# Kuga2.net
KiCad netlist of a schematic drawn in EAGLE
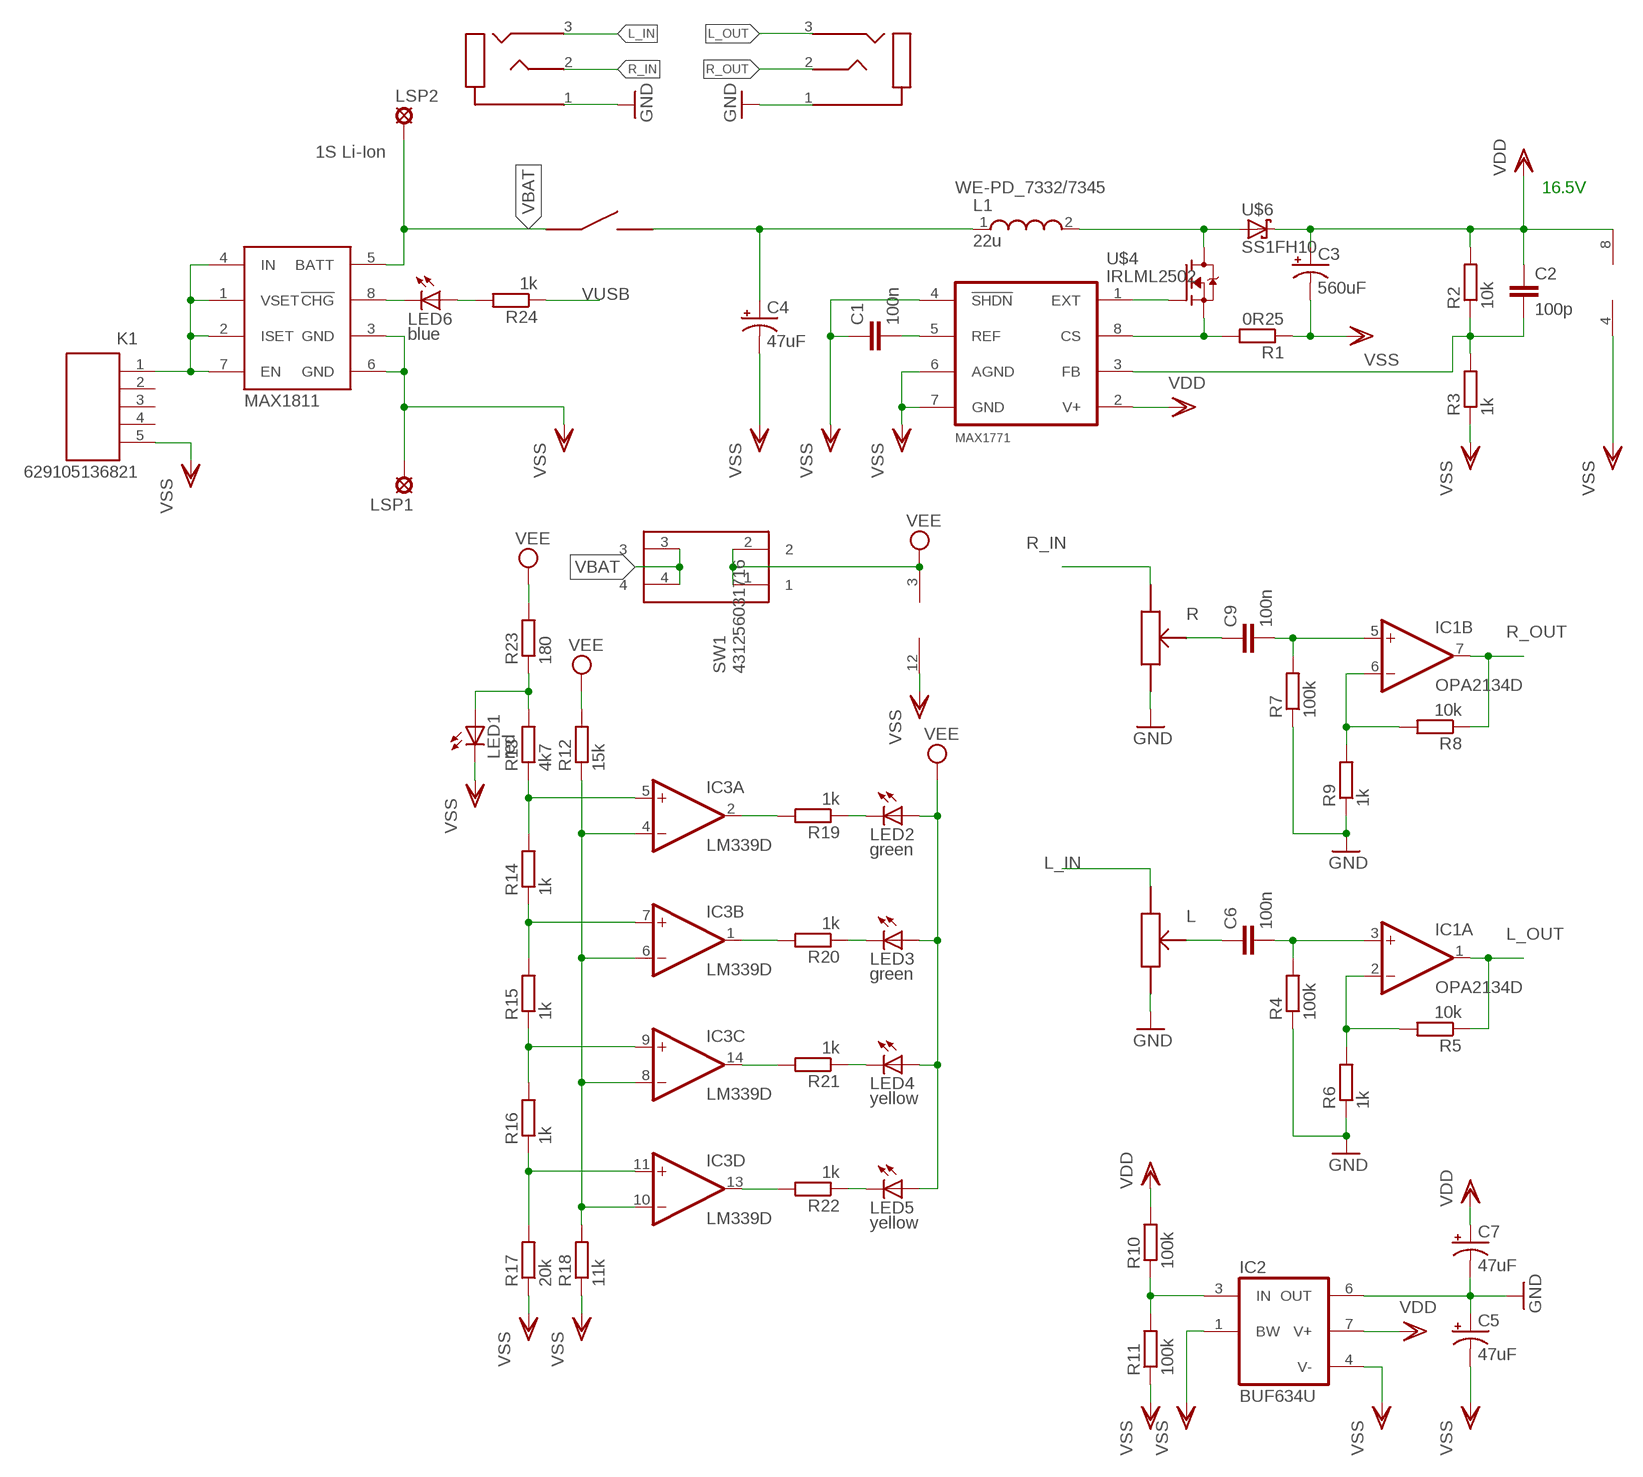
[diagram p0: schematic, sheet 1]

(export (version "E")
  (design (tool "Eeschema 10.0.6"))
  (components
    (comp (ref "C1")
      (value "100n")
      (footprint "eagle-import:C0603K")
      (libsource (lib "eagle-import") (part "C-EUC0603K"))
    )
    (comp (ref "C2")
      (value "100p")
      (footprint "eagle-import:C0603")
      (libsource (lib "eagle-import") (part "C-EUC0603"))
    )
    (comp (ref "C3")
      (value "560uF")
      (footprint "eagle-import:PANASONIC_G")
      (libsource (lib "eagle-import") (part "560UF-PANASONIC_G-25V-20%"))
    )
    (comp (ref "C4")
      (value "47uF")
      (footprint "eagle-import:PANASONIC_D")
      (libsource (lib "eagle-import") (part "47UF-POLAR-PANASONIC_D-35V-20%"))
    )
    (comp (ref "C5")
      (value "47uF")
      (footprint "eagle-import:PANASONIC_D")
      (libsource (lib "eagle-import") (part "47UF-POLAR-PANASONIC_D-35V-20%"))
    )
    (comp (ref "C6")
      (value "100n")
      (footprint "eagle-import:C1206")
      (libsource (lib "eagle-import") (part "C-EUC1206"))
    )
    (comp (ref "C7")
      (value "47uF")
      (footprint "eagle-import:PANASONIC_D")
      (libsource (lib "eagle-import") (part "47UF-POLAR-PANASONIC_D-35V-20%"))
    )
    (comp (ref "C9")
      (value "100n")
      (footprint "eagle-import:C1206")
      (libsource (lib "eagle-import") (part "C-EUC1206"))
    )
    (comp (ref "IC1")
      (value "OPA2134D")
      (footprint "eagle-import:SOIC8")
      (libsource (lib "eagle-import") (part "OPA2134D"))
    )
    (comp (ref "IC2")
      (value "BUF634U")
      (footprint "eagle-import:SO08")
      (fields (field (name "MF") "TEXAS INSTRUMENTS"))
      (libsource (lib "eagle-import") (part "BUF634U"))
    )
    (comp (ref "IC3")
      (value "LM339D")
      (footprint "eagle-import:SO14")
      (libsource (lib "eagle-import") (part "LM339D"))
    )
    (comp (ref "K1")
      (value "629105136821")
      (footprint "eagle-import:629105136821")
      (libsource (lib "eagle-import") (part "629105136821"))
    )
    (comp (ref "L1")
      (value "22u")
      (footprint "eagle-import:WE-PD_7332_7345")
      (libsource (lib "eagle-import") (part "WE-PD_7332/7345"))
    )
    (comp (ref "LED1")
      (value "red")
      (footprint "eagle-import:CHIP-LED0603")
      (libsource (lib "eagle-import") (part "LEDCHIP-LED0603"))
    )
    (comp (ref "LED2")
      (value "green")
      (footprint "eagle-import:CHIP-LED0603")
      (libsource (lib "eagle-import") (part "LEDCHIP-LED0603"))
    )
    (comp (ref "LED3")
      (value "green")
      (footprint "eagle-import:CHIP-LED0603")
      (libsource (lib "eagle-import") (part "LEDCHIP-LED0603"))
    )
    (comp (ref "LED4")
      (value "yellow")
      (footprint "eagle-import:CHIP-LED0603")
      (libsource (lib "eagle-import") (part "LEDCHIP-LED0603"))
    )
    (comp (ref "LED5")
      (value "yellow")
      (footprint "eagle-import:CHIP-LED0603")
      (libsource (lib "eagle-import") (part "LEDCHIP-LED0603"))
    )
    (comp (ref "LED6")
      (value "blue")
      (footprint "eagle-import:CHIP-LED0603")
      (libsource (lib "eagle-import") (part "LEDCHIP-LED0603"))
    )
    (comp (ref "LSP1")
      (value "LSP10")
      (footprint "eagle-import:LSP10")
      (libsource (lib "eagle-import") (part "LSP10"))
    )
    (comp (ref "LSP2")
      (value "LSP10")
      (footprint "eagle-import:LSP10")
      (libsource (lib "eagle-import") (part "LSP10"))
    )
    (comp (ref "MAX1771")
      (value "MAX1771")
      (footprint "eagle-import:SO-08")
      (libsource (lib "eagle-import") (part "MAX1771"))
    )
    (comp (ref "MAX1811")
      (value "MAX1811")
      (footprint "eagle-import:SO-08")
      (libsource (lib "eagle-import") (part "MAX1811"))
    )
    (comp (ref "R1")
      (value "0R25")
      (footprint "eagle-import:M3216")
      (libsource (lib "eagle-import") (part "R-EU_M3216"))
    )
    (comp (ref "R2")
      (value "10k")
      (footprint "eagle-import:R0603")
      (libsource (lib "eagle-import") (part "R-EU_R0603"))
    )
    (comp (ref "R3")
      (value "1k")
      (footprint "eagle-import:R0603")
      (libsource (lib "eagle-import") (part "R-EU_R0603"))
    )
    (comp (ref "R4")
      (value "100k")
      (footprint "eagle-import:R1206")
      (libsource (lib "eagle-import") (part "R-EU_R1206"))
    )
    (comp (ref "R5")
      (value "10k")
      (footprint "eagle-import:R1206")
      (libsource (lib "eagle-import") (part "R-EU_R1206"))
    )
    (comp (ref "R6")
      (value "1k")
      (footprint "eagle-import:R1206")
      (libsource (lib "eagle-import") (part "R-EU_R1206"))
    )
    (comp (ref "R7")
      (value "100k")
      (footprint "eagle-import:R1206")
      (libsource (lib "eagle-import") (part "R-EU_R1206"))
    )
    (comp (ref "R8")
      (value "10k")
      (footprint "eagle-import:R1206")
      (libsource (lib "eagle-import") (part "R-EU_R1206"))
    )
    (comp (ref "R9")
      (value "1k")
      (footprint "eagle-import:R1206")
      (libsource (lib "eagle-import") (part "R-EU_R1206"))
    )
    (comp (ref "R10")
      (value "100k")
      (footprint "eagle-import:R0603")
      (libsource (lib "eagle-import") (part "R-EU_R0603"))
    )
    (comp (ref "R11")
      (value "100k")
      (footprint "eagle-import:R0603")
      (libsource (lib "eagle-import") (part "R-EU_R0603"))
    )
    (comp (ref "R12")
      (value "15k")
      (footprint "eagle-import:R0603")
      (libsource (lib "eagle-import") (part "R-EU_R0603"))
    )
    (comp (ref "R13")
      (value "4k7")
      (footprint "eagle-import:R0603")
      (libsource (lib "eagle-import") (part "R-EU_R0603"))
    )
    (comp (ref "R14")
      (value "1k")
      (footprint "eagle-import:R0603")
      (libsource (lib "eagle-import") (part "R-EU_R0603"))
    )
    (comp (ref "R15")
      (value "1k")
      (footprint "eagle-import:R0603")
      (libsource (lib "eagle-import") (part "R-EU_R0603"))
    )
    (comp (ref "R16")
      (value "1k")
      (footprint "eagle-import:R0603")
      (libsource (lib "eagle-import") (part "R-EU_R0603"))
    )
    (comp (ref "R17")
      (value "20k")
      (footprint "eagle-import:R0603")
      (libsource (lib "eagle-import") (part "R-EU_R0603"))
    )
    (comp (ref "R18")
      (value "11k")
      (footprint "eagle-import:R0603")
      (libsource (lib "eagle-import") (part "R-EU_R0603"))
    )
    (comp (ref "R19")
      (value "1k")
      (footprint "eagle-import:R0603")
      (libsource (lib "eagle-import") (part "R-EU_R0603"))
    )
    (comp (ref "R20")
      (value "1k")
      (footprint "eagle-import:R0603")
      (libsource (lib "eagle-import") (part "R-EU_R0603"))
    )
    (comp (ref "R21")
      (value "1k")
      (footprint "eagle-import:R0603")
      (libsource (lib "eagle-import") (part "R-EU_R0603"))
    )
    (comp (ref "R22")
      (value "1k")
      (footprint "eagle-import:R0603")
      (libsource (lib "eagle-import") (part "R-EU_R0603"))
    )
    (comp (ref "R23")
      (value "180")
      (footprint "eagle-import:R0603")
      (libsource (lib "eagle-import") (part "R-EU_R0603"))
    )
    (comp (ref "R24")
      (value "1k")
      (footprint "eagle-import:R0603")
      (libsource (lib "eagle-import") (part "R-EU_R0603"))
    )
    (comp (ref "SW1")
      (value "431256031716")
      (footprint "eagle-import:431256031716")
      (libsource (lib "eagle-import") (part "431256031716"))
    )
    (comp (ref "U$1")
      (value "SJ1-3515-SMT-TR")
      (footprint "eagle-import:STX-35332-3N-TR")
      (libsource (lib "eagle-import") (part "SJ1-3515-SMT-TR"))
    )
    (comp (ref "U$2")
      (value "SJ1-3515-SMT-TR")
      (footprint "eagle-import:STX-35332-3N-TR")
      (libsource (lib "eagle-import") (part "SJ1-3515-SMT-TR"))
    )
    (comp (ref "U$4")
      (value "IRLML2502")
      (footprint "eagle-import:SOT23")
      (libsource (lib "eagle-import") (part "IRLML2502"))
    )
    (comp (ref "U$5")
      (value "PTR90")
      (footprint "eagle-import:PTR902")
      (libsource (lib "eagle-import") (part "PTR90"))
    )
    (comp (ref "U$6")
      (value "SS1FH10")
      (footprint "eagle-import:DO-219AB")
      (libsource (lib "eagle-import") (part "SS1FH10"))
    )
  )
  (nets
    (net (code "1") (name "/L") (class "Default")
      (node (ref "C6") (pin "1") (pinfunction "1_1") (pintype "passive"))
      (node (ref "U$5") (pin "R22") (pinfunction "12_R22") (pintype "bidirectional"))
    )
    (net (code "2") (name "/R") (class "Default")
      (node (ref "C9") (pin "1") (pinfunction "1_1") (pintype "passive"))
      (node (ref "U$5") (pin "R12") (pinfunction "12_R12") (pintype "bidirectional"))
    )
    (net (code "3") (name "/VUSB") (class "Default")
      (node (ref "K1") (pin "1") (pinfunction "1_1") (pintype "passive"))
      (node (ref "MAX1811") (pin "1") (pinfunction "VSET_1") (pintype "bidirectional"))
      (node (ref "MAX1811") (pin "2") (pinfunction "ISET_2") (pintype "bidirectional"))
      (node (ref "MAX1811") (pin "4") (pinfunction "IN_4") (pintype "bidirectional"))
      (node (ref "MAX1811") (pin "7") (pinfunction "EN_7") (pintype "bidirectional"))
      (node (ref "R24") (pin "1") (pinfunction "1_1") (pintype "passive"))
    )
    (net (code "4") (name "GND") (class "Default")
      (node (ref "C5") (pin "+") (pinfunction "+_+") (pintype "passive"))
      (node (ref "C7") (pin "-") (pinfunction "-_-") (pintype "passive"))
      (node (ref "IC2") (pin "6") (pinfunction "OUT_6") (pintype "output"))
      (node (ref "R4") (pin "1") (pinfunction "1_1") (pintype "passive"))
      (node (ref "R6") (pin "1") (pinfunction "1_1") (pintype "passive"))
      (node (ref "R7") (pin "1") (pinfunction "1_1") (pintype "passive"))
      (node (ref "R9") (pin "1") (pinfunction "1_1") (pintype "passive"))
      (node (ref "U$1") (pin "1") (pinfunction "SLEEVE_1") (pintype "bidirectional"))
      (node (ref "U$2") (pin "1") (pinfunction "SLEEVE_1") (pintype "bidirectional"))
      (node (ref "U$5") (pin "R13") (pinfunction "13_R13") (pintype "bidirectional"))
      (node (ref "U$5") (pin "R23") (pinfunction "13_R23") (pintype "bidirectional"))
    )
    (net (code "5") (name "L_IN") (class "Default")
      (node (ref "U$2") (pin "3") (pinfunction "RING_3") (pintype "bidirectional"))
      (node (ref "U$5") (pin "R21") (pinfunction "11_R21") (pintype "bidirectional"))
    )
    (net (code "6") (name "L_OUT") (class "Default")
      (node (ref "IC1") (pin "1") (pinfunction "OUT_1") (pintype "output"))
      (node (ref "R5") (pin "1") (pinfunction "1_1") (pintype "passive"))
      (node (ref "U$1") (pin "3") (pinfunction "RING_3") (pintype "bidirectional"))
    )
    (net (code "7") (name "Net-(IC1A-+IN)") (class "Default")
      (node (ref "C6") (pin "2") (pinfunction "2_2") (pintype "passive"))
      (node (ref "IC1") (pin "3") (pinfunction "+IN_3") (pintype "input"))
      (node (ref "R4") (pin "2") (pinfunction "2_2") (pintype "passive"))
    )
    (net (code "8") (name "Net-(IC1A--IN)") (class "Default")
      (node (ref "IC1") (pin "2") (pinfunction "-IN_2") (pintype "input"))
      (node (ref "R5") (pin "2") (pinfunction "2_2") (pintype "passive"))
      (node (ref "R6") (pin "2") (pinfunction "2_2") (pintype "passive"))
    )
    (net (code "9") (name "Net-(IC1B-+IN)") (class "Default")
      (node (ref "C9") (pin "2") (pinfunction "2_2") (pintype "passive"))
      (node (ref "IC1") (pin "5") (pinfunction "+IN_5") (pintype "input"))
      (node (ref "R7") (pin "2") (pinfunction "2_2") (pintype "passive"))
    )
    (net (code "10") (name "Net-(IC1B--IN)") (class "Default")
      (node (ref "IC1") (pin "6") (pinfunction "-IN_6") (pintype "input"))
      (node (ref "R8") (pin "2") (pinfunction "2_2") (pintype "passive"))
      (node (ref "R9") (pin "2") (pinfunction "2_2") (pintype "passive"))
    )
    (net (code "11") (name "Net-(IC2-IN)") (class "Default")
      (node (ref "IC2") (pin "3") (pinfunction "IN_3") (pintype "input"))
      (node (ref "R10") (pin "1") (pinfunction "1_1") (pintype "passive"))
      (node (ref "R11") (pin "2") (pinfunction "2_2") (pintype "passive"))
    )
    (net (code "12") (name "Net-(IC3A-+IN)") (class "Default")
      (node (ref "IC3") (pin "5") (pinfunction "+IN_5") (pintype "input"))
      (node (ref "R13") (pin "1") (pinfunction "1_1") (pintype "passive"))
      (node (ref "R14") (pin "2") (pinfunction "2_2") (pintype "passive"))
    )
    (net (code "13") (name "Net-(IC3A--IN)") (class "Default")
      (node (ref "IC3") (pin "10") (pinfunction "-IN_10") (pintype "input"))
      (node (ref "IC3") (pin "4") (pinfunction "-IN_4") (pintype "input"))
      (node (ref "IC3") (pin "6") (pinfunction "-IN_6") (pintype "input"))
      (node (ref "IC3") (pin "8") (pinfunction "-IN_8") (pintype "input"))
      (node (ref "R12") (pin "1") (pinfunction "1_1") (pintype "passive"))
      (node (ref "R18") (pin "2") (pinfunction "2_2") (pintype "passive"))
    )
    (net (code "14") (name "Net-(IC3A-OUT)") (class "Default")
      (node (ref "IC3") (pin "2") (pinfunction "OUT_2") (pintype "open_collector"))
      (node (ref "R19") (pin "2") (pinfunction "2_2") (pintype "passive"))
    )
    (net (code "15") (name "Net-(IC3B-+IN)") (class "Default")
      (node (ref "IC3") (pin "7") (pinfunction "+IN_7") (pintype "input"))
      (node (ref "R14") (pin "1") (pinfunction "1_1") (pintype "passive"))
      (node (ref "R15") (pin "2") (pinfunction "2_2") (pintype "passive"))
    )
    (net (code "16") (name "Net-(IC3B-OUT)") (class "Default")
      (node (ref "IC3") (pin "1") (pinfunction "OUT_1") (pintype "open_collector"))
      (node (ref "R20") (pin "2") (pinfunction "2_2") (pintype "passive"))
    )
    (net (code "17") (name "Net-(IC3C-+IN)") (class "Default")
      (node (ref "IC3") (pin "9") (pinfunction "+IN_9") (pintype "input"))
      (node (ref "R15") (pin "1") (pinfunction "1_1") (pintype "passive"))
      (node (ref "R16") (pin "2") (pinfunction "2_2") (pintype "passive"))
    )
    (net (code "18") (name "Net-(IC3C-OUT)") (class "Default")
      (node (ref "IC3") (pin "14") (pinfunction "OUT_14") (pintype "open_collector"))
      (node (ref "R21") (pin "2") (pinfunction "2_2") (pintype "passive"))
    )
    (net (code "19") (name "Net-(IC3D-+IN)") (class "Default")
      (node (ref "IC3") (pin "11") (pinfunction "+IN_11") (pintype "input"))
      (node (ref "R16") (pin "1") (pinfunction "1_1") (pintype "passive"))
      (node (ref "R17") (pin "2") (pinfunction "2_2") (pintype "passive"))
    )
    (net (code "20") (name "Net-(IC3D-OUT)") (class "Default")
      (node (ref "IC3") (pin "13") (pinfunction "OUT_13") (pintype "open_collector"))
      (node (ref "R22") (pin "2") (pinfunction "2_2") (pintype "passive"))
    )
    (net (code "21") (name "Net-(LED1-PadA)") (class "Default")
      (node (ref "LED1") (pin "A") (pinfunction "A_A") (pintype "passive"))
      (node (ref "R13") (pin "2") (pinfunction "2_2") (pintype "passive"))
      (node (ref "R23") (pin "1") (pinfunction "1_1") (pintype "passive"))
    )
    (net (code "22") (name "Net-(LED2-PadC)") (class "Default")
      (node (ref "LED2") (pin "C") (pinfunction "C_C") (pintype "passive"))
      (node (ref "R19") (pin "1") (pinfunction "1_1") (pintype "passive"))
    )
    (net (code "23") (name "Net-(LED3-PadC)") (class "Default")
      (node (ref "LED3") (pin "C") (pinfunction "C_C") (pintype "passive"))
      (node (ref "R20") (pin "1") (pinfunction "1_1") (pintype "passive"))
    )
    (net (code "24") (name "Net-(LED4-PadC)") (class "Default")
      (node (ref "LED4") (pin "C") (pinfunction "C_C") (pintype "passive"))
      (node (ref "R21") (pin "1") (pinfunction "1_1") (pintype "passive"))
    )
    (net (code "25") (name "Net-(LED5-PadC)") (class "Default")
      (node (ref "LED5") (pin "C") (pinfunction "C_C") (pintype "passive"))
      (node (ref "R22") (pin "1") (pinfunction "1_1") (pintype "passive"))
    )
    (net (code "26") (name "Net-(LED6-PadA)") (class "Default")
      (node (ref "LED6") (pin "A") (pinfunction "A_A") (pintype "passive"))
      (node (ref "R24") (pin "2") (pinfunction "2_2") (pintype "passive"))
    )
    (net (code "27") (name "Net-(MAX1771-CS)") (class "Default")
      (node (ref "MAX1771") (pin "8") (pinfunction "CS_8") (pintype "bidirectional"))
      (node (ref "R1") (pin "2") (pinfunction "2_2") (pintype "passive"))
      (node (ref "U$4") (pin "2") (pinfunction "S_2") (pintype "passive"))
    )
    (net (code "28") (name "Net-(MAX1771-EXT)") (class "Default")
      (node (ref "MAX1771") (pin "1") (pinfunction "EXT_1") (pintype "bidirectional"))
      (node (ref "U$4") (pin "1") (pinfunction "G_1") (pintype "passive"))
    )
    (net (code "29") (name "Net-(MAX1771-FB)") (class "Default")
      (node (ref "C2") (pin "2") (pinfunction "2_2") (pintype "passive"))
      (node (ref "MAX1771") (pin "3") (pinfunction "FB_3") (pintype "bidirectional"))
      (node (ref "R2") (pin "1") (pinfunction "1_1") (pintype "passive"))
      (node (ref "R3") (pin "2") (pinfunction "2_2") (pintype "passive"))
    )
    (net (code "30") (name "Net-(MAX1771-REF)") (class "Default")
      (node (ref "C1") (pin "2") (pinfunction "2_2") (pintype "passive"))
      (node (ref "MAX1771") (pin "5") (pinfunction "REF_5") (pintype "bidirectional"))
    )
    (net (code "31") (name "Net-(MAX1811-~{CHG})") (class "Default")
      (node (ref "LED6") (pin "C") (pinfunction "C_C") (pintype "passive"))
      (node (ref "MAX1811") (pin "8") (pinfunction "~{CHG}_8") (pintype "bidirectional"))
    )
    (net (code "32") (name "Net-(U$4-D)") (class "Default")
      (node (ref "L1") (pin "2") (pinfunction "2_2") (pintype "passive"))
      (node (ref "U$4") (pin "3") (pinfunction "D_3") (pintype "passive"))
      (node (ref "U$6") (pin "A") (pinfunction "A_A") (pintype "passive"))
    )
    (net (code "33") (name "Net-(U$5C-12)") (class "Default")
      (node (ref "C4") (pin "+") (pinfunction "+_+") (pintype "passive"))
      (node (ref "L1") (pin "1") (pinfunction "1_1") (pintype "passive"))
      (node (ref "U$5") (pin "SW2") (pinfunction "12_SW2") (pintype "bidirectional"))
    )
    (net (code "34") (name "R_IN") (class "Default")
      (node (ref "U$2") (pin "2") (pinfunction "TIP_2") (pintype "bidirectional"))
      (node (ref "U$5") (pin "R11") (pinfunction "11_R11") (pintype "bidirectional"))
    )
    (net (code "35") (name "R_OUT") (class "Default")
      (node (ref "IC1") (pin "7") (pinfunction "OUT_7") (pintype "output"))
      (node (ref "R8") (pin "1") (pinfunction "1_1") (pintype "passive"))
      (node (ref "U$1") (pin "2") (pinfunction "TIP_2") (pintype "bidirectional"))
    )
    (net (code "36") (name "VBAT") (class "Default")
      (node (ref "LSP2") (pin "MP") (pinfunction "MP_MP") (pintype "passive"))
      (node (ref "MAX1811") (pin "5") (pinfunction "BATT_5") (pintype "bidirectional"))
      (node (ref "SW1") (pin "3") (pinfunction "3_3") (pintype "bidirectional"))
      (node (ref "SW1") (pin "4") (pinfunction "4_4") (pintype "bidirectional"))
      (node (ref "U$5") (pin "SW1") (pinfunction "11_SW1") (pintype "bidirectional"))
    )
    (net (code "37") (name "VDD") (class "Default")
      (node (ref "C2") (pin "1") (pinfunction "1_1") (pintype "passive"))
      (node (ref "C3") (pin "+") (pinfunction "+_+") (pintype "passive"))
      (node (ref "C7") (pin "+") (pinfunction "+_+") (pintype "passive"))
      (node (ref "IC1") (pin "8") (pinfunction "V+_8") (pintype "power_in"))
      (node (ref "IC2") (pin "7") (pinfunction "V+_7") (pintype "power_in"))
      (node (ref "MAX1771") (pin "2") (pinfunction "V+_2") (pintype "bidirectional"))
      (node (ref "R10") (pin "2") (pinfunction "2_2") (pintype "passive"))
      (node (ref "R2") (pin "2") (pinfunction "2_2") (pintype "passive"))
      (node (ref "U$6") (pin "K") (pinfunction "C_K") (pintype "passive"))
    )
    (net (code "38") (name "VEE") (class "Default")
      (node (ref "IC3") (pin "3") (pinfunction "V+_3") (pintype "power_in"))
      (node (ref "LED2") (pin "A") (pinfunction "A_A") (pintype "passive"))
      (node (ref "LED3") (pin "A") (pinfunction "A_A") (pintype "passive"))
      (node (ref "LED4") (pin "A") (pinfunction "A_A") (pintype "passive"))
      (node (ref "LED5") (pin "A") (pinfunction "A_A") (pintype "passive"))
      (node (ref "R12") (pin "2") (pinfunction "2_2") (pintype "passive"))
      (node (ref "R23") (pin "2") (pinfunction "2_2") (pintype "passive"))
      (node (ref "SW1") (pin "1") (pinfunction "1_1") (pintype "bidirectional"))
      (node (ref "SW1") (pin "2") (pinfunction "2_2") (pintype "bidirectional"))
    )
    (net (code "39") (name "VSS") (class "Default")
      (node (ref "C1") (pin "1") (pinfunction "1_1") (pintype "passive"))
      (node (ref "C3") (pin "-") (pinfunction "-_-") (pintype "passive"))
      (node (ref "C4") (pin "-") (pinfunction "-_-") (pintype "passive"))
      (node (ref "C5") (pin "-") (pinfunction "-_-") (pintype "passive"))
      (node (ref "IC1") (pin "4") (pinfunction "V-_4") (pintype "power_in"))
      (node (ref "IC2") (pin "1") (pinfunction "BW_1") (pintype "passive"))
      (node (ref "IC2") (pin "4") (pinfunction "V-_4") (pintype "power_in"))
      (node (ref "IC3") (pin "12") (pinfunction "GND_12") (pintype "power_in"))
      (node (ref "K1") (pin "5") (pinfunction "5_5") (pintype "passive"))
      (node (ref "LED1") (pin "C") (pinfunction "C_C") (pintype "passive"))
      (node (ref "LSP1") (pin "MP") (pinfunction "MP_MP") (pintype "passive"))
      (node (ref "MAX1771") (pin "4") (pinfunction "~{SHDN}_4") (pintype "bidirectional"))
      (node (ref "MAX1771") (pin "6") (pinfunction "AGND_6") (pintype "bidirectional"))
      (node (ref "MAX1771") (pin "7") (pinfunction "GND_7") (pintype "bidirectional"))
      (node (ref "MAX1811") (pin "3") (pinfunction "GND_3") (pintype "bidirectional"))
      (node (ref "MAX1811") (pin "6") (pinfunction "GND_6") (pintype "bidirectional"))
      (node (ref "R1") (pin "1") (pinfunction "1_1") (pintype "passive"))
      (node (ref "R11") (pin "1") (pinfunction "1_1") (pintype "passive"))
      (node (ref "R17") (pin "1") (pinfunction "1_1") (pintype "passive"))
      (node (ref "R18") (pin "1") (pinfunction "1_1") (pintype "passive"))
      (node (ref "R3") (pin "1") (pinfunction "1_1") (pintype "passive"))
    )
    (net (code "40") (name "unconnected-(K1-Pad2)") (class "Default")
      (node (ref "K1") (pin "2") (pinfunction "2_2") (pintype "passive"))
    )
    (net (code "41") (name "unconnected-(K1-Pad3)") (class "Default")
      (node (ref "K1") (pin "3") (pinfunction "3_3") (pintype "passive"))
    )
    (net (code "42") (name "unconnected-(K1-Pad4)") (class "Default")
      (node (ref "K1") (pin "4") (pinfunction "4_4") (pintype "passive"))
    )
  )
)
